# Gateway.net
KiCad netlist of a schematic drawn in Altium Designer
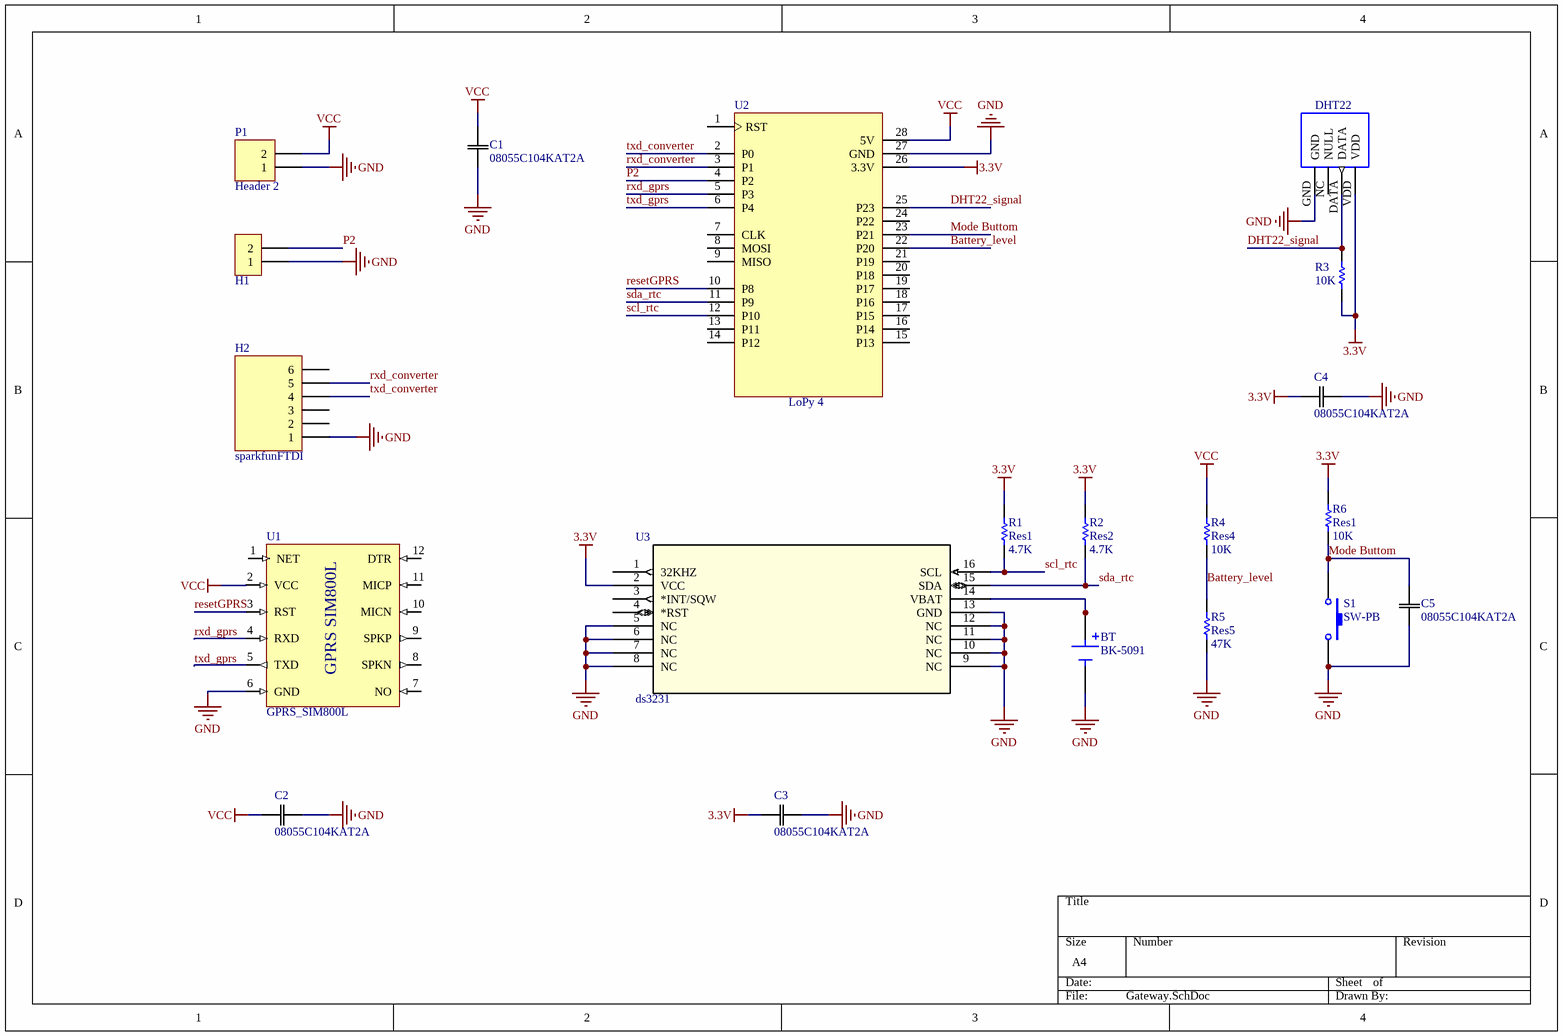
[diagram p0: Gateway.SchDoc]

(export (version "E")
  (design (tool "Eeschema 10.0.6"))
  (components
    (comp (ref "BT")
      (value "BK-5091")
      (footprint "SnapEDApcb:BAT_BK-5091")
      (description "Battery Retainer Coin, 11.6mm 1 Cell PC Pin")
      (fields (field (name "MF") "MPD") (field (name "DIGI-KEY_PART_NUMBER") "BK-5091-ND"))
      (libsource (lib "SnapEDAsch") (part "BK-5091"))
    )
    (comp (ref "C1")
      (value "08055C104KAT2A")
      (footprint "CAP_X7R_0805_AVX")
      (description "No Description Available")
      (fields (field (name "COPYRIGHT") "Copyright (C) 2018 Accelerated Designs. All rights reserved"))
      (libsource (lib "cap_0805") (part "08055C104KAT2A"))
    )
    (comp (ref "C2")
      (value "08055C104KAT2A")
      (footprint "CAP_X7R_0805_AVX")
      (description "No Description Available")
      (fields (field (name "COPYRIGHT") "Copyright (C) 2018 Accelerated Designs. All rights reserved"))
      (libsource (lib "cap_0805") (part "08055C104KAT2A"))
    )
    (comp (ref "C3")
      (value "08055C104KAT2A")
      (footprint "CAP_X7R_0805_AVX")
      (description "No Description Available")
      (fields (field (name "COPYRIGHT") "Copyright (C) 2018 Accelerated Designs. All rights reserved"))
      (libsource (lib "cap_0805") (part "08055C104KAT2A"))
    )
    (comp (ref "C4")
      (value "08055C104KAT2A")
      (footprint "CAP_X7R_0805_AVX")
      (description "No Description Available")
      (fields (field (name "COPYRIGHT") "Copyright (C) 2018 Accelerated Designs. All rights reserved"))
      (libsource (lib "cap_0805") (part "08055C104KAT2A"))
    )
    (comp (ref "C5")
      (value "08055C104KAT2A")
      (footprint "CAP_X7R_0805_AVX")
      (description "No Description Available")
      (fields (field (name "COPYRIGHT") "Copyright (C) 2018 Accelerated Designs. All rights reserved"))
      (libsource (lib "cap_0805") (part "08055C104KAT2A"))
    )
    (comp (ref "H1")
      (value "Header")
      (footprint "Header 1X2")
      (description "Header 2 pin")
      (libsource (lib "Conectores") (part "Header 2"))
    )
    (comp (ref "H2")
      (value "sparkfunFTDI")
      (footprint "sparkfunFTDI")
      (description "Header, 6-Pin")
      (fields (field (name "PUBLISHER") "Altium Limited"))
      (libsource (lib "Conectores") (part "sparkfunFTDI"))
    )
    (comp (ref "J1")
      (value "DHT22")
      (footprint "DHT22:DHT22")
      (description "Capacitive-type humidity and temperature module/sensor")
      (fields (field (name "MF") "Aosong Electronics"))
      (libsource (lib "DHT22") (part "DHT22"))
    )
    (comp (ref "P1")
      (value "Header 2")
      (footprint "BORNERA25-2")
      (description "Header, 2-Pin")
      (fields (field (name "PUBLISHER") "Altium Limited"))
      (libsource (lib "Miscellaneous Connectors_3D") (part "Header 2"))
    )
    (comp (ref "R1")
      (value "Res1")
      (footprint "0805")
      (description "Resistor")
      (fields (field (name "ALTIUM_VALUE") "4.7K") (field (name "PUBLISHER") "Altium Limited"))
      (libsource (lib "Miscellaneous Devices") (part "Res1"))
    )
    (comp (ref "R2")
      (value "Res2")
      (footprint "0805")
      (description "Resistor")
      (fields (field (name "ALTIUM_VALUE") "4.7K") (field (name "PUBLISHER") "Altium Limited"))
      (libsource (lib "Miscellaneous Devices") (part "Res1"))
    )
    (comp (ref "R3")
      (value "10K")
      (footprint "0805")
      (description "Resistor")
      (fields (field (name "Comment") "Res3") (field (name "PUBLISHER") "Altium Limited"))
      (libsource (lib "Miscellaneous Devices") (part "Res1"))
    )
    (comp (ref "R4")
      (value "Res4")
      (footprint "0805")
      (description "Resistor")
      (fields (field (name "ALTIUM_VALUE") "10K") (field (name "PUBLISHER") "Altium Limited"))
      (libsource (lib "Miscellaneous Devices") (part "Res1"))
    )
    (comp (ref "R5")
      (value "Res5")
      (footprint "0805")
      (description "Resistor")
      (fields (field (name "ALTIUM_VALUE") "47K") (field (name "PUBLISHER") "Altium Limited"))
      (libsource (lib "Miscellaneous Devices") (part "Res1"))
    )
    (comp (ref "R6")
      (value "Res1")
      (footprint "0805")
      (description "Resistor")
      (fields (field (name "ALTIUM_VALUE") "10K") (field (name "PUBLISHER") "Altium Limited"))
      (libsource (lib "Miscellaneous Devices") (part "Res1"))
    )
    (comp (ref "S1")
      (value "SW-PB")
      (footprint "BUTTON-1-SMD")
      (description "Switch")
      (fields (field (name "PUBLISHER") "Altium Limited"))
      (libsource (lib "Miscellaneous Devices") (part "SW-PB"))
    )
    (comp (ref "U1")
      (value "GPRS_SIM800L")
      (footprint "PCBComponent_1")
      (libsource (lib "GPRS_SIM800L") (part "Component_1"))
    )
    (comp (ref "U2")
      (value "LoPy 4")
      (footprint "LoPy")
      (fields (field (name "PUBLISHER") "Altium Limited"))
      (libsource (lib "LoPy") (part "LoPy"))
    )
    (comp (ref "U3")
      (value "ds3231")
      (footprint "21-0042B_16_MXM")
      (description "No Description Available")
      (fields
        (field (name "MANUFACTURER_PART_NUMBER") "ds3231s#")
        (field (name "COPYRIGHT") "Copyright (C) 2018 Accelerated Designs. All rights reserved")
      )
      (libsource (lib "2021-01-26_16-05-58") (part "ds3231s#"))
    )
  )
  (nets
    (net (code "1") (name "/Battery_level") (class "Default")
      (node (ref "R4") (pin "2") (pinfunction "2_2") (pintype "passive"))
      (node (ref "R5") (pin "1") (pinfunction "1_1") (pintype "passive"))
      (node (ref "U2") (pin "22") (pinfunction "P20_22") (pintype "passive"))
    )
    (net (code "2") (name "/DHT22_signal") (class "Default")
      (node (ref "J1") (pin "DATA") (pinfunction "DATA_DATA") (pintype "output"))
      (node (ref "R3") (pin "1") (pinfunction "1_1") (pintype "passive"))
      (node (ref "U2") (pin "25") (pinfunction "P23_25") (pintype "passive"))
    )
    (net (code "3") (name "/Mode Buttom") (class "Default")
      (node (ref "C5") (pin "2") (pinfunction "2_2") (pintype "passive"))
      (node (ref "R6") (pin "2") (pinfunction "2_2") (pintype "passive"))
      (node (ref "S1") (pin "1") (pinfunction "1_1") (pintype "passive"))
      (node (ref "U2") (pin "23") (pinfunction "P21_23") (pintype "passive"))
    )
    (net (code "4") (name "/P2") (class "Default")
      (node (ref "H1") (pin "2") (pinfunction "2_2") (pintype "passive"))
      (node (ref "U2") (pin "4") (pinfunction "P2_4") (pintype "passive"))
    )
    (net (code "5") (name "/resetGPRS") (class "Default")
      (node (ref "U1") (pin "3") (pinfunction "RST_3") (pintype "input"))
      (node (ref "U2") (pin "10") (pinfunction "P8_10") (pintype "passive"))
    )
    (net (code "6") (name "/rxd_converter") (class "Default")
      (node (ref "H2") (pin "5") (pinfunction "5_5") (pintype "passive"))
      (node (ref "U2") (pin "3") (pinfunction "P1_3") (pintype "passive"))
    )
    (net (code "7") (name "/rxd_gprs") (class "Default")
      (node (ref "U1") (pin "4") (pinfunction "RXD_4") (pintype "input"))
      (node (ref "U2") (pin "5") (pinfunction "P3_5") (pintype "passive"))
    )
    (net (code "8") (name "/scl_rtc") (class "Default")
      (node (ref "R1") (pin "2") (pinfunction "2_2") (pintype "passive"))
      (node (ref "U2") (pin "12") (pinfunction "P10_12") (pintype "passive"))
      (node (ref "U3") (pin "16") (pinfunction "SCL_16") (pintype "input"))
    )
    (net (code "9") (name "/sda_rtc") (class "Default")
      (node (ref "R2") (pin "2") (pinfunction "2_2") (pintype "passive"))
      (node (ref "U2") (pin "11") (pinfunction "P9_11") (pintype "passive"))
      (node (ref "U3") (pin "15") (pinfunction "SDA_15") (pintype "bidirectional"))
    )
    (net (code "10") (name "/txd_converter") (class "Default")
      (node (ref "H2") (pin "4") (pinfunction "4_4") (pintype "passive"))
      (node (ref "U2") (pin "2") (pinfunction "P0_2") (pintype "power_in"))
    )
    (net (code "11") (name "/txd_gprs") (class "Default")
      (node (ref "U1") (pin "5") (pinfunction "TXD_5") (pintype "output"))
      (node (ref "U2") (pin "6") (pinfunction "P4_6") (pintype "passive"))
    )
    (net (code "12") (name "3.3V") (class "Default")
      (node (ref "C3") (pin "2") (pinfunction "2_2") (pintype "passive"))
      (node (ref "C4") (pin "1") (pinfunction "1_1") (pintype "passive"))
      (node (ref "J1") (pin "VDD") (pinfunction "VDD_VDD") (pintype "power_in"))
      (node (ref "R1") (pin "1") (pinfunction "1_1") (pintype "passive"))
      (node (ref "R2") (pin "1") (pinfunction "1_1") (pintype "passive"))
      (node (ref "R3") (pin "2") (pinfunction "2_2") (pintype "passive"))
      (node (ref "R6") (pin "1") (pinfunction "1_1") (pintype "passive"))
      (node (ref "U2") (pin "26") (pinfunction "3.3V_26") (pintype "passive"))
      (node (ref "U3") (pin "2") (pinfunction "VCC_2") (pintype "power_in"))
    )
    (net (code "13") (name "GND") (class "Default")
      (node (ref "BT") (pin "NEG") (pinfunction "NEG_NEG") (pintype "passive"))
      (node (ref "C1") (pin "1") (pinfunction "1_1") (pintype "passive"))
      (node (ref "C2") (pin "1") (pinfunction "1_1") (pintype "passive"))
      (node (ref "C3") (pin "1") (pinfunction "1_1") (pintype "passive"))
      (node (ref "C4") (pin "2") (pinfunction "2_2") (pintype "passive"))
      (node (ref "C5") (pin "1") (pinfunction "1_1") (pintype "passive"))
      (node (ref "H1") (pin "1") (pinfunction "1_1") (pintype "passive"))
      (node (ref "H2") (pin "1") (pinfunction "1_1") (pintype "passive"))
      (node (ref "J1") (pin "GND") (pinfunction "GND_GND") (pintype "power_in"))
      (node (ref "P1") (pin "1") (pinfunction "1_1") (pintype "passive"))
      (node (ref "R5") (pin "2") (pinfunction "2_2") (pintype "passive"))
      (node (ref "S1") (pin "2") (pinfunction "2_2") (pintype "passive"))
      (node (ref "U1") (pin "6") (pinfunction "GND_6") (pintype "input"))
      (node (ref "U2") (pin "27") (pinfunction "GND_27") (pintype "passive"))
      (node (ref "U3") (pin "10") (pinfunction "NC_10") (pintype "passive"))
      (node (ref "U3") (pin "11") (pinfunction "NC_11") (pintype "passive"))
      (node (ref "U3") (pin "12") (pinfunction "NC_12") (pintype "passive"))
      (node (ref "U3") (pin "13") (pinfunction "GND_13") (pintype "power_in"))
      (node (ref "U3") (pin "5") (pinfunction "NC_5") (pintype "passive"))
      (node (ref "U3") (pin "6") (pinfunction "NC_6") (pintype "passive"))
      (node (ref "U3") (pin "7") (pinfunction "NC_7") (pintype "passive"))
      (node (ref "U3") (pin "8") (pinfunction "NC_8") (pintype "passive"))
      (node (ref "U3") (pin "9") (pinfunction "NC_9") (pintype "passive"))
    )
    (net (code "14") (name "Net-(U3-VBAT)") (class "Default")
      (node (ref "BT") (pin "1+") (pinfunction "POS_1+") (pintype "passive"))
      (node (ref "BT") (pin "2+") (pinfunction "POS_2+") (pintype "passive"))
      (node (ref "U3") (pin "14") (pinfunction "VBAT_14") (pintype "power_in"))
    )
    (net (code "15") (name "VCC") (class "Default")
      (node (ref "C1") (pin "2") (pinfunction "2_2") (pintype "passive"))
      (node (ref "C2") (pin "2") (pinfunction "2_2") (pintype "passive"))
      (node (ref "P1") (pin "2") (pinfunction "2_2") (pintype "passive"))
      (node (ref "R4") (pin "1") (pinfunction "1_1") (pintype "passive"))
      (node (ref "U1") (pin "2") (pinfunction "VCC_2") (pintype "input"))
      (node (ref "U2") (pin "28") (pinfunction "5V_28") (pintype "passive"))
    )
    (net (code "16") (name "unconnected-(H2-Pad2)") (class "Default")
      (node (ref "H2") (pin "2") (pinfunction "2_2") (pintype "passive"))
    )
    (net (code "17") (name "unconnected-(H2-Pad3)") (class "Default")
      (node (ref "H2") (pin "3") (pinfunction "3_3") (pintype "passive"))
    )
    (net (code "18") (name "unconnected-(H2-Pad6)") (class "Default")
      (node (ref "H2") (pin "6") (pinfunction "6_6") (pintype "passive"))
    )
    (net (code "19") (name "unconnected-(J1-NULL-PadNC)") (class "Default")
      (node (ref "J1") (pin "NC") (pinfunction "NULL_NC") (pintype "passive"))
    )
    (net (code "20") (name "unconnected-(U1-DTR-Pad12)") (class "Default")
      (node (ref "U1") (pin "12") (pinfunction "DTR_12") (pintype "input"))
    )
    (net (code "21") (name "unconnected-(U1-MICN-Pad10)") (class "Default")
      (node (ref "U1") (pin "10") (pinfunction "MICN_10") (pintype "input"))
    )
    (net (code "22") (name "unconnected-(U1-MICP-Pad11)") (class "Default")
      (node (ref "U1") (pin "11") (pinfunction "MICP_11") (pintype "input"))
    )
    (net (code "23") (name "unconnected-(U1-NET-Pad1)") (class "Default")
      (node (ref "U1") (pin "1") (pinfunction "NET_1") (pintype "input"))
    )
    (net (code "24") (name "unconnected-(U1-NO-Pad7)") (class "Default")
      (node (ref "U1") (pin "7") (pinfunction "NO_7") (pintype "input"))
    )
    (net (code "25") (name "unconnected-(U1-SPKN-Pad8)") (class "Default")
      (node (ref "U1") (pin "8") (pinfunction "SPKN_8") (pintype "output"))
    )
    (net (code "26") (name "unconnected-(U1-SPKP-Pad9)") (class "Default")
      (node (ref "U1") (pin "9") (pinfunction "SPKP_9") (pintype "output"))
    )
    (net (code "27") (name "unconnected-(U2-CLK-Pad7)") (class "Default")
      (node (ref "U2") (pin "7") (pinfunction "CLK_7") (pintype "passive"))
    )
    (net (code "28") (name "unconnected-(U2-MISO-Pad9)") (class "Default")
      (node (ref "U2") (pin "9") (pinfunction "MISO_9") (pintype "passive"))
    )
    (net (code "29") (name "unconnected-(U2-MOSI-Pad8)") (class "Default")
      (node (ref "U2") (pin "8") (pinfunction "MOSI_8") (pintype "passive"))
    )
    (net (code "30") (name "unconnected-(U2-P11-Pad13)") (class "Default")
      (node (ref "U2") (pin "13") (pinfunction "P11_13") (pintype "passive"))
    )
    (net (code "31") (name "unconnected-(U2-P12-Pad14)") (class "Default")
      (node (ref "U2") (pin "14") (pinfunction "P12_14") (pintype "passive"))
    )
    (net (code "32") (name "unconnected-(U2-P13-Pad15)") (class "Default")
      (node (ref "U2") (pin "15") (pinfunction "P13_15") (pintype "passive"))
    )
    (net (code "33") (name "unconnected-(U2-P14-Pad16)") (class "Default")
      (node (ref "U2") (pin "16") (pinfunction "P14_16") (pintype "passive"))
    )
    (net (code "34") (name "unconnected-(U2-P15-Pad17)") (class "Default")
      (node (ref "U2") (pin "17") (pinfunction "P15_17") (pintype "passive"))
    )
    (net (code "35") (name "unconnected-(U2-P16-Pad18)") (class "Default")
      (node (ref "U2") (pin "18") (pinfunction "P16_18") (pintype "passive"))
    )
    (net (code "36") (name "unconnected-(U2-P17-Pad19)") (class "Default")
      (node (ref "U2") (pin "19") (pinfunction "P17_19") (pintype "passive"))
    )
    (net (code "37") (name "unconnected-(U2-P18-Pad20)") (class "Default")
      (node (ref "U2") (pin "20") (pinfunction "P18_20") (pintype "passive"))
    )
    (net (code "38") (name "unconnected-(U2-P19-Pad21)") (class "Default")
      (node (ref "U2") (pin "21") (pinfunction "P19_21") (pintype "passive"))
    )
    (net (code "39") (name "unconnected-(U2-P22-Pad24)") (class "Default")
      (node (ref "U2") (pin "24") (pinfunction "P22_24") (pintype "passive"))
    )
    (net (code "40") (name "unconnected-(U2-RST-Pad1)") (class "Default")
      (node (ref "U2") (pin "1") (pinfunction "RST_1") (pintype "passive"))
    )
    (net (code "41") (name "unconnected-(U3-*INT{slash}SQW-Pad3)") (class "Default")
      (node (ref "U3") (pin "3") (pinfunction "*INT/SQW_3") (pintype "output"))
    )
    (net (code "42") (name "unconnected-(U3-*RST-Pad4)") (class "Default")
      (node (ref "U3") (pin "4") (pinfunction "*RST_4") (pintype "bidirectional"))
    )
    (net (code "43") (name "unconnected-(U3-32KHZ-Pad1)") (class "Default")
      (node (ref "U3") (pin "1") (pinfunction "32KHZ_1") (pintype "output"))
    )
  )
)
